# obc_spi_to_i2c.net
KiCad netlist of a schematic drawn in Altium Designer
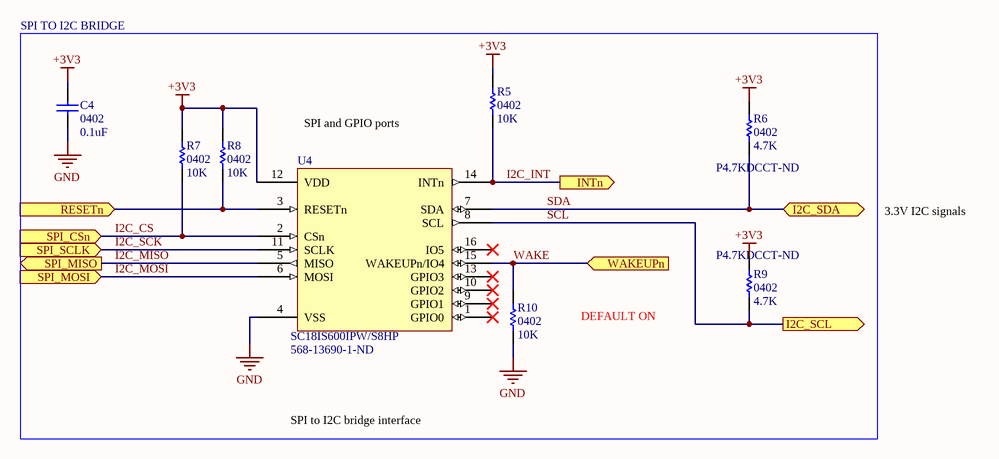
[diagram p0: obc_spi_to_i2c.SchDoc]

(export (version "E")
  (design (tool "Eeschema 10.0.6"))
  (components
    (comp (ref "C4")
      (value "0402")
      (footprint "CAP0402R")
      (description "0402 capacitor")
      (fields (field (name "ALTIUM_VALUE") "0.1uF"))
      (libsource (lib "heron-general") (part "CAP0402"))
    )
    (comp (ref "R5")
      (value "0402")
      (footprint "RES0402R")
      (description "0402 resistor")
      (fields (field (name "ALTIUM_VALUE") "10K"))
      (libsource (lib "heron-general") (part "RES0402"))
    )
    (comp (ref "R6")
      (value "0402")
      (footprint "RES0402R")
      (description "0402 resistor")
      (fields
        (field (name "ALTIUM_VALUE") "4.7K")
        (field (name "SUPPLIER PART NUMBER 1") "P4.7KDCCT-ND")
        (field (name "MANUFACTURER") "Panasonic")
        (field (name "MANUFACTURER PART NUMBER") "ERA-2AEB472X")
      )
      (libsource (lib "heron-general") (part "RES0402"))
    )
    (comp (ref "R7")
      (value "0402")
      (footprint "RES0402R")
      (description "0402 resistor")
      (fields (field (name "ALTIUM_VALUE") "10K"))
      (libsource (lib "heron-general") (part "RES0402"))
    )
    (comp (ref "R8")
      (value "0402")
      (footprint "RES0402R")
      (description "0402 resistor")
      (fields (field (name "ALTIUM_VALUE") "10K"))
      (libsource (lib "heron-general") (part "RES0402"))
    )
    (comp (ref "R9")
      (value "0402")
      (footprint "RES0402R")
      (description "0402 resistor")
      (fields
        (field (name "ALTIUM_VALUE") "4.7K")
        (field (name "SUPPLIER PART NUMBER 1") "P4.7KDCCT-ND")
        (field (name "MANUFACTURER") "Panasonic")
        (field (name "MANUFACTURER PART NUMBER") "ERA-2AEB472X")
      )
      (libsource (lib "heron-general") (part "RES0402"))
    )
    (comp (ref "R10")
      (value "0402")
      (footprint "RES0402R")
      (description "0402 resistor")
      (fields (field (name "ALTIUM_VALUE") "10K"))
      (libsource (lib "heron-general") (part "RES0402"))
    )
    (comp (ref "U4")
      (value "SC18IS600IPW/S8HP")
      (footprint "TSOP65P640X110-16N")
      (description "SPI to I2C bridge.")
      (fields (field (name "SUPPLIER PART NUMBER 1") "568-13690-1-ND"))
      (libsource (lib "ICs") (part "SC18IS600IPW/S8HP"))
    )
  )
  (nets
    (net (code "1") (name "+3V3") (class "Default")
      (node (ref "C4") (pin "2") (pinfunction "2_2") (pintype "passive"))
      (node (ref "R5") (pin "2") (pinfunction "2_2") (pintype "passive"))
      (node (ref "R6") (pin "2") (pinfunction "2_2") (pintype "passive"))
      (node (ref "R7") (pin "2") (pinfunction "2_2") (pintype "passive"))
      (node (ref "R8") (pin "2") (pinfunction "2_2") (pintype "passive"))
      (node (ref "R9") (pin "2") (pinfunction "2_2") (pintype "passive"))
      (node (ref "U4") (pin "12") (pinfunction "VDD_12") (pintype "power_in"))
    )
    (net (code "2") (name "/I2C_CS") (class "Default")
      (node (ref "R7") (pin "1") (pinfunction "1_1") (pintype "passive"))
      (node (ref "U4") (pin "2") (pinfunction "CSn_2") (pintype "input"))
    )
    (net (code "3") (name "/I2C_INT") (class "Default")
      (node (ref "R5") (pin "1") (pinfunction "1_1") (pintype "passive"))
      (node (ref "U4") (pin "14") (pinfunction "INTn_14") (pintype "output"))
    )
    (net (code "4") (name "/I2C_MISO") (class "Default")
      (node (ref "U4") (pin "5") (pinfunction "MISO_5") (pintype "output"))
    )
    (net (code "5") (name "/I2C_MOSI") (class "Default")
      (node (ref "U4") (pin "6") (pinfunction "MOSI_6") (pintype "input"))
    )
    (net (code "6") (name "/I2C_SCK") (class "Default")
      (node (ref "U4") (pin "11") (pinfunction "SCLK_11") (pintype "input"))
    )
    (net (code "7") (name "/RESETn") (class "Default")
      (node (ref "R8") (pin "1") (pinfunction "1_1") (pintype "passive"))
      (node (ref "U4") (pin "3") (pinfunction "RESETn_3") (pintype "input"))
    )
    (net (code "8") (name "/SCL") (class "Default")
      (node (ref "R9") (pin "1") (pinfunction "1_1") (pintype "passive"))
      (node (ref "U4") (pin "8") (pinfunction "SCL_8") (pintype "output"))
    )
    (net (code "9") (name "/SDA") (class "Default")
      (node (ref "R6") (pin "1") (pinfunction "1_1") (pintype "passive"))
      (node (ref "U4") (pin "7") (pinfunction "SDA_7") (pintype "bidirectional"))
    )
    (net (code "10") (name "/WAKE") (class "Default")
      (node (ref "R10") (pin "2") (pinfunction "2_2") (pintype "passive"))
      (node (ref "U4") (pin "15") (pinfunction "WAKEUPn/IO4_15") (pintype "bidirectional"))
    )
    (net (code "11") (name "GND") (class "Default")
      (node (ref "C4") (pin "1") (pinfunction "1_1") (pintype "passive"))
      (node (ref "R10") (pin "1") (pinfunction "1_1") (pintype "passive"))
      (node (ref "U4") (pin "4") (pinfunction "VSS_4") (pintype "power_in"))
    )
    (net (code "12") (name "unconnected-(U4-GPIO0-Pad1)") (class "Default")
      (node (ref "U4") (pin "1") (pinfunction "GPIO0_1") (pintype "bidirectional+no_connect"))
    )
    (net (code "13") (name "unconnected-(U4-GPIO1-Pad9)") (class "Default")
      (node (ref "U4") (pin "9") (pinfunction "GPIO1_9") (pintype "bidirectional+no_connect"))
    )
    (net (code "14") (name "unconnected-(U4-GPIO2-Pad10)") (class "Default")
      (node (ref "U4") (pin "10") (pinfunction "GPIO2_10") (pintype "bidirectional+no_connect"))
    )
    (net (code "15") (name "unconnected-(U4-GPIO3-Pad13)") (class "Default")
      (node (ref "U4") (pin "13") (pinfunction "GPIO3_13") (pintype "bidirectional+no_connect"))
    )
    (net (code "16") (name "unconnected-(U4-IO5-Pad16)") (class "Default")
      (node (ref "U4") (pin "16") (pinfunction "IO5_16") (pintype "bidirectional+no_connect"))
    )
  )
)
